# RGBW_controller.net
KiCad netlist of a schematic drawn in Altium Designer
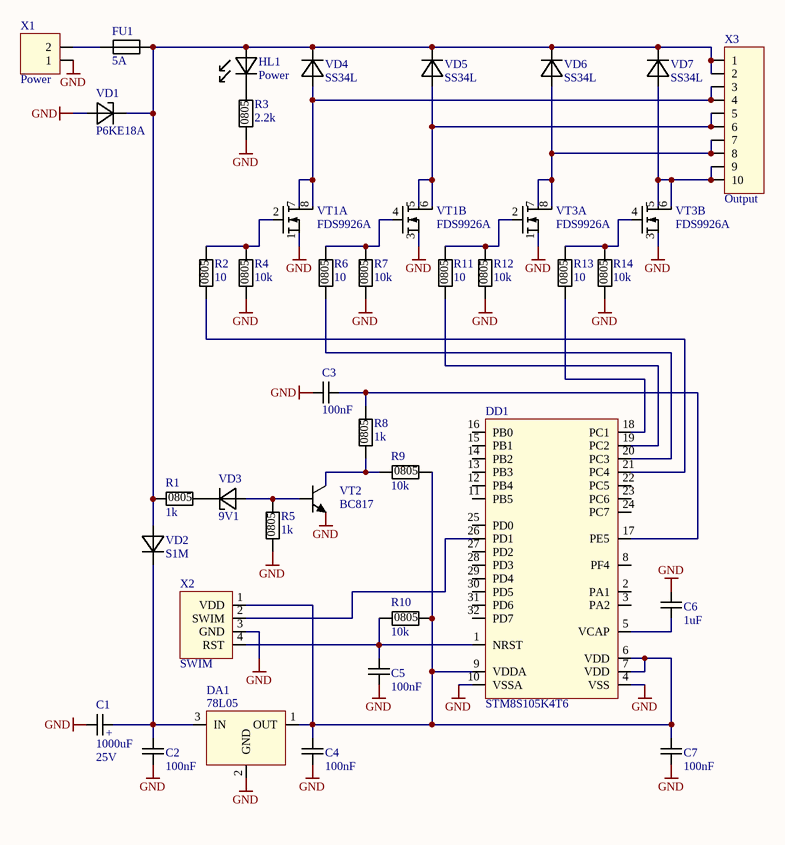
[diagram p0: RGBW_controller.SchDoc]

(export (version "E")
  (design (tool "Eeschema 10.0.6"))
  (components
    (comp (ref "C1")
      (value "1000uF")
      (footprint "CapEl 10x20x5 axial")
      (description "Electrolytic capacitor")
      (fields (field (name "VOLTAGE") "25V") (field (name "PART NUMBER") "CapEL_10x20x5_axial"))
      (libsource (lib "Library") (part "CapEl"))
    )
    (comp (ref "C2")
      (value "100nF")
      (footprint "C0805")
      (description "0805 SMD capacitors")
      (fields (field (name "PART NUMBER") "C0805"))
      (libsource (lib "Library") (part "Capacitor"))
    )
    (comp (ref "C3")
      (value "100nF")
      (footprint "C0805")
      (description "0805 SMD capacitors")
      (fields (field (name "PART NUMBER") "C0805"))
      (libsource (lib "Library") (part "Capacitor"))
    )
    (comp (ref "C4")
      (value "100nF")
      (footprint "C0805")
      (description "0805 SMD capacitors")
      (fields (field (name "PART NUMBER") "C0805"))
      (libsource (lib "Library") (part "Capacitor"))
    )
    (comp (ref "C5")
      (value "100nF")
      (footprint "C0805")
      (description "0805 SMD capacitors")
      (fields (field (name "PART NUMBER") "C0805"))
      (libsource (lib "Library") (part "Capacitor"))
    )
    (comp (ref "C6")
      (value "1uF")
      (footprint "C0805")
      (description "0805 SMD capacitors")
      (fields (field (name "PART NUMBER") "C0805"))
      (libsource (lib "Library") (part "Capacitor"))
    )
    (comp (ref "C7")
      (value "100nF")
      (footprint "C0805")
      (description "0805 SMD capacitors")
      (fields (field (name "PART NUMBER") "C0805"))
      (libsource (lib "Library") (part "Capacitor"))
    )
    (comp (ref "DA1")
      (value "78L05")
      (footprint "TO92 line")
      (description "Positive Linear Voltage Regulator")
      (fields (field (name "PART NUMBER") "L78L"))
      (libsource (lib "Library") (part "78xx OGI"))
    )
    (comp (ref "DD1")
      (value "STM8S105K4T6")
      (footprint "TQFP32")
      (description "STM8 MCU with 16kB Flash")
      (libsource (lib "Library") (part "STM8S105K"))
    )
    (comp (ref "FU1")
      (value "5A")
      (footprint "Fuse 4x10")
      (description "PCB Leaded Fuse 4x10 15mm pitch")
      (fields (field (name "PART NUMBER") "Fuse_4x10"))
      (libsource (lib "Library") (part "Fuse"))
    )
    (comp (ref "HL1")
      (value "Power")
      (footprint "LED 3mm green")
      (description "3mm DIP green LED")
      (fields (field (name "PART NUMBER") "LED 3mm green"))
      (libsource (lib "Library") (part "LED"))
    )
    (comp (ref "R1")
      (value "1k")
      (footprint "R0805")
      (description "0805 SMD 1/8W resistor")
      (fields (field (name "PART NUMBER") "R0805"))
      (libsource (lib "Library") (part "Resistor 0805"))
    )
    (comp (ref "R2")
      (value "10")
      (footprint "R0805")
      (description "0805 SMD 1/8W resistor")
      (fields (field (name "PART NUMBER") "R0805"))
      (libsource (lib "Library") (part "Resistor 0805"))
    )
    (comp (ref "R3")
      (value "2.2k")
      (footprint "R0805")
      (description "0805 SMD 1/8W resistor")
      (fields (field (name "PART NUMBER") "R0805"))
      (libsource (lib "Library") (part "Resistor 0805"))
    )
    (comp (ref "R4")
      (value "10k")
      (footprint "R0805")
      (description "0805 SMD 1/8W resistor")
      (fields (field (name "PART NUMBER") "R0805"))
      (libsource (lib "Library") (part "Resistor 0805"))
    )
    (comp (ref "R5")
      (value "1k")
      (footprint "R0805")
      (description "0805 SMD 1/8W resistor")
      (fields (field (name "PART NUMBER") "R0805"))
      (libsource (lib "Library") (part "Resistor 0805"))
    )
    (comp (ref "R6")
      (value "10")
      (footprint "R0805")
      (description "0805 SMD 1/8W resistor")
      (fields (field (name "PART NUMBER") "R0805"))
      (libsource (lib "Library") (part "Resistor 0805"))
    )
    (comp (ref "R7")
      (value "10k")
      (footprint "R0805")
      (description "0805 SMD 1/8W resistor")
      (fields (field (name "PART NUMBER") "R0805"))
      (libsource (lib "Library") (part "Resistor 0805"))
    )
    (comp (ref "R8")
      (value "1k")
      (footprint "R0805")
      (description "0805 SMD 1/8W resistor")
      (fields (field (name "PART NUMBER") "R0805"))
      (libsource (lib "Library") (part "Resistor 0805"))
    )
    (comp (ref "R9")
      (value "10k")
      (footprint "R0805")
      (description "0805 SMD 1/8W resistor")
      (fields (field (name "PART NUMBER") "R0805"))
      (libsource (lib "Library") (part "Resistor 0805"))
    )
    (comp (ref "R10")
      (value "10k")
      (footprint "R0805")
      (description "0805 SMD 1/8W resistor")
      (fields (field (name "PART NUMBER") "R0805"))
      (libsource (lib "Library") (part "Resistor 0805"))
    )
    (comp (ref "R11")
      (value "10")
      (footprint "R0805")
      (description "0805 SMD 1/8W resistor")
      (fields (field (name "PART NUMBER") "R0805"))
      (libsource (lib "Library") (part "Resistor 0805"))
    )
    (comp (ref "R12")
      (value "10k")
      (footprint "R0805")
      (description "0805 SMD 1/8W resistor")
      (fields (field (name "PART NUMBER") "R0805"))
      (libsource (lib "Library") (part "Resistor 0805"))
    )
    (comp (ref "R13")
      (value "10")
      (footprint "R0805")
      (description "0805 SMD 1/8W resistor")
      (fields (field (name "PART NUMBER") "R0805"))
      (libsource (lib "Library") (part "Resistor 0805"))
    )
    (comp (ref "R14")
      (value "10k")
      (footprint "R0805")
      (description "0805 SMD 1/8W resistor")
      (fields (field (name "PART NUMBER") "R0805"))
      (libsource (lib "Library") (part "Resistor 0805"))
    )
    (comp (ref "VD1")
      (value "P6KE18A")
      (footprint "DO15")
      (description "18V 600W THT Unidirectional Supressor")
      (libsource (lib "Library") (part "Diode Zener"))
    )
    (comp (ref "VD2")
      (value "S1M")
      (footprint "SMA")
      (description "1A Surface Mount Rectifier")
      (libsource (lib "Library") (part "Diode"))
    )
    (comp (ref "VD3")
      (value "9V1")
      (footprint "SOD80")
      (description "500mW SMD Zener Diode")
      (fields (field (name "PART NUMBER") "BZV55"))
      (libsource (lib "Library") (part "Diode Zener"))
    )
    (comp (ref "VD4")
      (value "SS34L")
      (footprint "SMA")
      (description "3A Low Case Schottky Barrier Diode")
      (libsource (lib "Library") (part "Diode"))
    )
    (comp (ref "VD5")
      (value "SS34L")
      (footprint "SMA")
      (description "3A Low Case Schottky Barrier Diode")
      (libsource (lib "Library") (part "Diode"))
    )
    (comp (ref "VD6")
      (value "SS34L")
      (footprint "SMA")
      (description "3A Low Case Schottky Barrier Diode")
      (libsource (lib "Library") (part "Diode"))
    )
    (comp (ref "VD7")
      (value "SS34L")
      (footprint "SMA")
      (description "3A Low Case Schottky Barrier Diode")
      (libsource (lib "Library") (part "Diode"))
    )
    (comp (ref "VT1")
      (value "FDS9926A")
      (footprint "SO8")
      (description "Dual 20V 6.5A SO8 SMD n-MOSFET transistor with Rds=30mOhm")
      (libsource (lib "Library") (part "FDS9926"))
    )
    (comp (ref "VT2")
      (value "BC817")
      (footprint "SOT23-3")
      (description "45V 500mA SOT23-3 SMD NPN transistor with h21>100")
      (libsource (lib "Library") (part "NPN_BEC"))
    )
    (comp (ref "VT3")
      (value "FDS9926A")
      (footprint "SO8")
      (description "Dual 20V 6.5A SO8 SMD n-MOSFET transistor with Rds=30mOhm")
      (libsource (lib "Library") (part "FDS9926"))
    )
    (comp (ref "X1")
      (value "Power")
      (footprint "DG301-5,0-2P")
      (description "2 pin Screw Terminal PCB Block")
      (fields (field (name "PART NUMBER") "DG301-5,0-2P"))
      (libsource (lib "Library") (part "Connector 2 pin"))
    )
    (comp (ref "X2")
      (value "SWIM")
      (footprint "PLS4")
      (description "4 pin SWIM connector for STM8 MCU programming")
      (libsource (lib "Library") (part "Connector SWIM"))
    )
    (comp (ref "X3")
      (value "Output")
      (footprint "DG380-3,81-10P")
      (description "10 pin Screw Terminal PCB Block")
      (fields (field (name "PART NUMBER") "DG380-3,81-10P"))
      (libsource (lib "Library") (part "Connector 10 pin"))
    )
  )
  (nets
    (net (code "1") (name "GND") (class "Default")
      (node (ref "C1") (pin "2") (pinfunction "2_2") (pintype "passive"))
      (node (ref "C2") (pin "2") (pinfunction "2_2") (pintype "passive"))
      (node (ref "C3") (pin "2") (pinfunction "2_2") (pintype "passive"))
      (node (ref "C4") (pin "2") (pinfunction "2_2") (pintype "passive"))
      (node (ref "C5") (pin "1") (pinfunction "1_1") (pintype "passive"))
      (node (ref "C6") (pin "2") (pinfunction "2_2") (pintype "passive"))
      (node (ref "C7") (pin "1") (pinfunction "1_1") (pintype "passive"))
      (node (ref "DA1") (pin "2") (pinfunction "GND_2") (pintype "passive"))
      (node (ref "DD1") (pin "10") (pinfunction "VSSA_10") (pintype "passive"))
      (node (ref "DD1") (pin "4") (pinfunction "VSS_4") (pintype "passive"))
      (node (ref "R12") (pin "1") (pinfunction "1_1") (pintype "passive"))
      (node (ref "R14") (pin "1") (pinfunction "1_1") (pintype "passive"))
      (node (ref "R3") (pin "1") (pinfunction "1_1") (pintype "passive"))
      (node (ref "R4") (pin "1") (pinfunction "1_1") (pintype "passive"))
      (node (ref "R5") (pin "1") (pinfunction "1_1") (pintype "passive"))
      (node (ref "R7") (pin "1") (pinfunction "1_1") (pintype "passive"))
      (node (ref "VD1") (pin "1") (pinfunction "A_1") (pintype "passive"))
      (node (ref "VT1") (pin "1") (pinfunction "S_1") (pintype "passive"))
      (node (ref "VT1") (pin "3") (pinfunction "S_3") (pintype "passive"))
      (node (ref "VT2") (pin "2") (pinfunction "E_2") (pintype "passive"))
      (node (ref "VT3") (pin "1") (pinfunction "S_1") (pintype "passive"))
      (node (ref "VT3") (pin "3") (pinfunction "S_3") (pintype "passive"))
      (node (ref "X1") (pin "1") (pinfunction "1_1") (pintype "passive"))
      (node (ref "X2") (pin "3") (pinfunction "GND_3") (pintype "passive"))
    )
    (net (code "2") (name "Net-(DA1-IN)") (class "Default")
      (node (ref "C1") (pin "1") (pinfunction "1_1") (pintype "passive"))
      (node (ref "C2") (pin "1") (pinfunction "1_1") (pintype "passive"))
      (node (ref "DA1") (pin "3") (pinfunction "IN_3") (pintype "passive"))
      (node (ref "VD2") (pin "2") (pinfunction "K_2") (pintype "passive"))
    )
    (net (code "3") (name "Net-(DA1-OUT)") (class "Default")
      (node (ref "C4") (pin "1") (pinfunction "1_1") (pintype "passive"))
      (node (ref "C7") (pin "2") (pinfunction "2_2") (pintype "passive"))
      (node (ref "DA1") (pin "1") (pinfunction "OUT_1") (pintype "passive"))
      (node (ref "DD1") (pin "6") (pinfunction "VDD_6") (pintype "passive"))
      (node (ref "DD1") (pin "7") (pinfunction "VDD_7") (pintype "passive"))
      (node (ref "DD1") (pin "9") (pinfunction "VDDA_9") (pintype "passive"))
      (node (ref "R10") (pin "2") (pinfunction "2_2") (pintype "passive"))
      (node (ref "R9") (pin "2") (pinfunction "2_2") (pintype "passive"))
      (node (ref "X2") (pin "1") (pinfunction "VDD_1") (pintype "passive"))
    )
    (net (code "4") (name "Net-(DD1-NRST)") (class "Default")
      (node (ref "C5") (pin "2") (pinfunction "2_2") (pintype "passive"))
      (node (ref "DD1") (pin "1") (pinfunction "NRST_1") (pintype "passive"))
      (node (ref "R10") (pin "1") (pinfunction "1_1") (pintype "passive"))
      (node (ref "X2") (pin "4") (pinfunction "RST_4") (pintype "passive"))
    )
    (net (code "5") (name "Net-(DD1-PC1)") (class "Default")
      (node (ref "DD1") (pin "18") (pinfunction "PC1_18") (pintype "passive"))
      (node (ref "R13") (pin "1") (pinfunction "1_1") (pintype "passive"))
    )
    (net (code "6") (name "Net-(DD1-PC2)") (class "Default")
      (node (ref "DD1") (pin "19") (pinfunction "PC2_19") (pintype "passive"))
      (node (ref "R11") (pin "1") (pinfunction "1_1") (pintype "passive"))
    )
    (net (code "7") (name "Net-(DD1-PC3)") (class "Default")
      (node (ref "DD1") (pin "20") (pinfunction "PC3_20") (pintype "passive"))
      (node (ref "R6") (pin "1") (pinfunction "1_1") (pintype "passive"))
    )
    (net (code "8") (name "Net-(DD1-PC4)") (class "Default")
      (node (ref "DD1") (pin "21") (pinfunction "PC4_21") (pintype "passive"))
      (node (ref "R2") (pin "1") (pinfunction "1_1") (pintype "passive"))
    )
    (net (code "9") (name "Net-(DD1-PD1)") (class "Default")
      (node (ref "DD1") (pin "26") (pinfunction "PD1_26") (pintype "passive"))
      (node (ref "X2") (pin "2") (pinfunction "SWIM_2") (pintype "passive"))
    )
    (net (code "10") (name "Net-(DD1-PE5)") (class "Default")
      (node (ref "C3") (pin "1") (pinfunction "1_1") (pintype "passive"))
      (node (ref "DD1") (pin "17") (pinfunction "PE5_17") (pintype "passive"))
      (node (ref "R8") (pin "2") (pinfunction "2_2") (pintype "passive"))
    )
    (net (code "11") (name "Net-(DD1-VCAP)") (class "Default")
      (node (ref "C6") (pin "1") (pinfunction "1_1") (pintype "passive"))
      (node (ref "DD1") (pin "5") (pinfunction "VCAP_5") (pintype "passive"))
    )
    (net (code "12") (name "Net-(FU1-Pad1)") (class "Default")
      (node (ref "FU1") (pin "1") (pinfunction "1_1") (pintype "passive"))
      (node (ref "X1") (pin "2") (pinfunction "2_2") (pintype "passive"))
    )
    (net (code "13") (name "Net-(HL1-A)") (class "Default")
      (node (ref "FU1") (pin "2") (pinfunction "2_2") (pintype "passive"))
      (node (ref "HL1") (pin "1") (pinfunction "A_1") (pintype "passive"))
      (node (ref "R1") (pin "1") (pinfunction "1_1") (pintype "passive"))
      (node (ref "VD1") (pin "2") (pinfunction "K_2") (pintype "passive"))
      (node (ref "VD2") (pin "1") (pinfunction "A_1") (pintype "passive"))
      (node (ref "VD4") (pin "2") (pinfunction "K_2") (pintype "passive"))
      (node (ref "VD5") (pin "2") (pinfunction "K_2") (pintype "passive"))
      (node (ref "VD6") (pin "2") (pinfunction "K_2") (pintype "passive"))
      (node (ref "VD7") (pin "2") (pinfunction "K_2") (pintype "passive"))
      (node (ref "X3") (pin "1") (pinfunction "1_1") (pintype "passive"))
      (node (ref "X3") (pin "2") (pinfunction "2_2") (pintype "passive"))
    )
    (net (code "14") (name "Net-(HL1-K)") (class "Default")
      (node (ref "HL1") (pin "2") (pinfunction "K_2") (pintype "passive"))
      (node (ref "R3") (pin "2") (pinfunction "2_2") (pintype "passive"))
    )
    (net (code "15") (name "Net-(VD3-A)") (class "Default")
      (node (ref "R5") (pin "2") (pinfunction "2_2") (pintype "passive"))
      (node (ref "VD3") (pin "1") (pinfunction "A_1") (pintype "passive"))
      (node (ref "VT2") (pin "1") (pinfunction "B_1") (pintype "passive"))
    )
    (net (code "16") (name "Net-(VD3-K)") (class "Default")
      (node (ref "R1") (pin "2") (pinfunction "2_2") (pintype "passive"))
      (node (ref "VD3") (pin "2") (pinfunction "K_2") (pintype "passive"))
    )
    (net (code "17") (name "Net-(VD4-A)") (class "Default")
      (node (ref "VD4") (pin "1") (pinfunction "A_1") (pintype "passive"))
      (node (ref "VT1") (pin "7") (pinfunction "D1_7") (pintype "passive"))
      (node (ref "VT1") (pin "8") (pinfunction "D2_8") (pintype "passive"))
      (node (ref "X3") (pin "3") (pinfunction "3_3") (pintype "passive"))
      (node (ref "X3") (pin "4") (pinfunction "4_4") (pintype "passive"))
    )
    (net (code "18") (name "Net-(VD5-A)") (class "Default")
      (node (ref "VD5") (pin "1") (pinfunction "A_1") (pintype "passive"))
      (node (ref "VT1") (pin "5") (pinfunction "D1_5") (pintype "passive"))
      (node (ref "VT1") (pin "6") (pinfunction "D2_6") (pintype "passive"))
      (node (ref "X3") (pin "5") (pinfunction "5_5") (pintype "passive"))
      (node (ref "X3") (pin "6") (pinfunction "6_6") (pintype "passive"))
    )
    (net (code "19") (name "Net-(VD6-A)") (class "Default")
      (node (ref "VD6") (pin "1") (pinfunction "A_1") (pintype "passive"))
      (node (ref "VT3") (pin "7") (pinfunction "D1_7") (pintype "passive"))
      (node (ref "VT3") (pin "8") (pinfunction "D2_8") (pintype "passive"))
      (node (ref "X3") (pin "7") (pinfunction "7_7") (pintype "passive"))
      (node (ref "X3") (pin "8") (pinfunction "8_8") (pintype "passive"))
    )
    (net (code "20") (name "Net-(VD7-A)") (class "Default")
      (node (ref "VD7") (pin "1") (pinfunction "A_1") (pintype "passive"))
      (node (ref "VT3") (pin "5") (pinfunction "D1_5") (pintype "passive"))
      (node (ref "VT3") (pin "6") (pinfunction "D2_6") (pintype "passive"))
      (node (ref "X3") (pin "10") (pinfunction "10_10") (pintype "passive"))
      (node (ref "X3") (pin "9") (pinfunction "9_9") (pintype "passive"))
    )
    (net (code "21") (name "Net-(VT1A-G)") (class "Default")
      (node (ref "R2") (pin "2") (pinfunction "2_2") (pintype "passive"))
      (node (ref "R4") (pin "2") (pinfunction "2_2") (pintype "passive"))
      (node (ref "VT1") (pin "2") (pinfunction "G_2") (pintype "passive"))
    )
    (net (code "22") (name "Net-(VT1B-G)") (class "Default")
      (node (ref "R6") (pin "2") (pinfunction "2_2") (pintype "passive"))
      (node (ref "R7") (pin "2") (pinfunction "2_2") (pintype "passive"))
      (node (ref "VT1") (pin "4") (pinfunction "G_4") (pintype "passive"))
    )
    (net (code "23") (name "Net-(VT2-C)") (class "Default")
      (node (ref "R8") (pin "1") (pinfunction "1_1") (pintype "passive"))
      (node (ref "R9") (pin "1") (pinfunction "1_1") (pintype "passive"))
      (node (ref "VT2") (pin "3") (pinfunction "C_3") (pintype "passive"))
    )
    (net (code "24") (name "Net-(VT3A-G)") (class "Default")
      (node (ref "R11") (pin "2") (pinfunction "2_2") (pintype "passive"))
      (node (ref "R12") (pin "2") (pinfunction "2_2") (pintype "passive"))
      (node (ref "VT3") (pin "2") (pinfunction "G_2") (pintype "passive"))
    )
    (net (code "25") (name "Net-(VT3B-G)") (class "Default")
      (node (ref "R13") (pin "2") (pinfunction "2_2") (pintype "passive"))
      (node (ref "R14") (pin "2") (pinfunction "2_2") (pintype "passive"))
      (node (ref "VT3") (pin "4") (pinfunction "G_4") (pintype "passive"))
    )
    (net (code "26") (name "unconnected-(DD1-PA1-Pad2)") (class "Default")
      (node (ref "DD1") (pin "2") (pinfunction "PA1_2") (pintype "passive"))
    )
    (net (code "27") (name "unconnected-(DD1-PA2-Pad3)") (class "Default")
      (node (ref "DD1") (pin "3") (pinfunction "PA2_3") (pintype "passive"))
    )
    (net (code "28") (name "unconnected-(DD1-PB0-Pad16)") (class "Default")
      (node (ref "DD1") (pin "16") (pinfunction "PB0_16") (pintype "passive"))
    )
    (net (code "29") (name "unconnected-(DD1-PB1-Pad15)") (class "Default")
      (node (ref "DD1") (pin "15") (pinfunction "PB1_15") (pintype "passive"))
    )
    (net (code "30") (name "unconnected-(DD1-PB2-Pad14)") (class "Default")
      (node (ref "DD1") (pin "14") (pinfunction "PB2_14") (pintype "passive"))
    )
    (net (code "31") (name "unconnected-(DD1-PB3-Pad13)") (class "Default")
      (node (ref "DD1") (pin "13") (pinfunction "PB3_13") (pintype "passive"))
    )
    (net (code "32") (name "unconnected-(DD1-PB4-Pad12)") (class "Default")
      (node (ref "DD1") (pin "12") (pinfunction "PB4_12") (pintype "passive"))
    )
    (net (code "33") (name "unconnected-(DD1-PB5-Pad11)") (class "Default")
      (node (ref "DD1") (pin "11") (pinfunction "PB5_11") (pintype "passive"))
    )
    (net (code "34") (name "unconnected-(DD1-PC5-Pad22)") (class "Default")
      (node (ref "DD1") (pin "22") (pinfunction "PC5_22") (pintype "passive"))
    )
    (net (code "35") (name "unconnected-(DD1-PC6-Pad23)") (class "Default")
      (node (ref "DD1") (pin "23") (pinfunction "PC6_23") (pintype "passive"))
    )
    (net (code "36") (name "unconnected-(DD1-PC7-Pad24)") (class "Default")
      (node (ref "DD1") (pin "24") (pinfunction "PC7_24") (pintype "passive"))
    )
    (net (code "37") (name "unconnected-(DD1-PD0-Pad25)") (class "Default")
      (node (ref "DD1") (pin "25") (pinfunction "PD0_25") (pintype "passive"))
    )
    (net (code "38") (name "unconnected-(DD1-PD2-Pad27)") (class "Default")
      (node (ref "DD1") (pin "27") (pinfunction "PD2_27") (pintype "passive"))
    )
    (net (code "39") (name "unconnected-(DD1-PD3-Pad28)") (class "Default")
      (node (ref "DD1") (pin "28") (pinfunction "PD3_28") (pintype "passive"))
    )
    (net (code "40") (name "unconnected-(DD1-PD4-Pad29)") (class "Default")
      (node (ref "DD1") (pin "29") (pinfunction "PD4_29") (pintype "passive"))
    )
    (net (code "41") (name "unconnected-(DD1-PD5-Pad30)") (class "Default")
      (node (ref "DD1") (pin "30") (pinfunction "PD5_30") (pintype "passive"))
    )
    (net (code "42") (name "unconnected-(DD1-PD6-Pad31)") (class "Default")
      (node (ref "DD1") (pin "31") (pinfunction "PD6_31") (pintype "passive"))
    )
    (net (code "43") (name "unconnected-(DD1-PD7-Pad32)") (class "Default")
      (node (ref "DD1") (pin "32") (pinfunction "PD7_32") (pintype "passive"))
    )
    (net (code "44") (name "unconnected-(DD1-PF4-Pad8)") (class "Default")
      (node (ref "DD1") (pin "8") (pinfunction "PF4_8") (pintype "passive"))
    )
  )
)
